# SOP-8_1_PCB.net
KiCad netlist of a schematic drawn in EAGLE
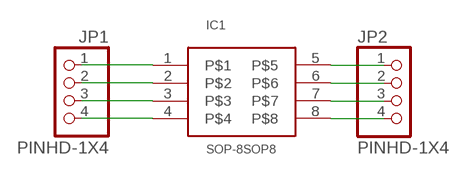
[diagram p0: schematic, sheet 1]

(export (version "E")
  (design (tool "Eeschema 10.0.6"))
  (components
    (comp (ref "IC1")
      (value "SOP-8SOP8")
      (footprint "eagle-import:SOP-8")
      (fields (field (name "MF") "Microchip") (field (name "MP") "AT24C02"))
      (libsource (lib "eagle-import") (part "SOP-8SOP8"))
    )
    (comp (ref "JP1")
      (value "PINHD-1X4")
      (footprint "eagle-import:1X04")
      (libsource (lib "eagle-import") (part "PINHD-1X4"))
    )
    (comp (ref "JP2")
      (value "PINHD-1X4")
      (footprint "eagle-import:1X04")
      (libsource (lib "eagle-import") (part "PINHD-1X4"))
    )
  )
  (nets
    (net (code "1") (name "Net-(IC1-P$1)") (class "Default")
      (node (ref "IC1") (pin "1") (pinfunction "P$1_1") (pintype "bidirectional"))
      (node (ref "JP1") (pin "1") (pinfunction "1_1") (pintype "passive"))
    )
    (net (code "2") (name "Net-(IC1-P$2)") (class "Default")
      (node (ref "IC1") (pin "2") (pinfunction "P$2_2") (pintype "bidirectional"))
      (node (ref "JP1") (pin "2") (pinfunction "2_2") (pintype "passive"))
    )
    (net (code "3") (name "Net-(IC1-P$3)") (class "Default")
      (node (ref "IC1") (pin "3") (pinfunction "P$3_3") (pintype "bidirectional"))
      (node (ref "JP1") (pin "3") (pinfunction "3_3") (pintype "passive"))
    )
    (net (code "4") (name "Net-(IC1-P$4)") (class "Default")
      (node (ref "IC1") (pin "4") (pinfunction "P$4_4") (pintype "bidirectional"))
      (node (ref "JP1") (pin "4") (pinfunction "4_4") (pintype "passive"))
    )
    (net (code "5") (name "Net-(IC1-P$5)") (class "Default")
      (node (ref "IC1") (pin "5") (pinfunction "P$5_5") (pintype "bidirectional"))
      (node (ref "JP2") (pin "1") (pinfunction "1_1") (pintype "passive"))
    )
    (net (code "6") (name "Net-(IC1-P$6)") (class "Default")
      (node (ref "IC1") (pin "6") (pinfunction "P$6_6") (pintype "bidirectional"))
      (node (ref "JP2") (pin "2") (pinfunction "2_2") (pintype "passive"))
    )
    (net (code "7") (name "Net-(IC1-P$7)") (class "Default")
      (node (ref "IC1") (pin "7") (pinfunction "P$7_7") (pintype "bidirectional"))
      (node (ref "JP2") (pin "3") (pinfunction "3_3") (pintype "passive"))
    )
    (net (code "8") (name "Net-(IC1-P$8)") (class "Default")
      (node (ref "IC1") (pin "8") (pinfunction "P$8_8") (pintype "bidirectional"))
      (node (ref "JP2") (pin "4") (pinfunction "4_4") (pintype "passive"))
    )
  )
)
